# dual_opamp_proto_board.net
KiCad netlist of a schematic drawn in EAGLE
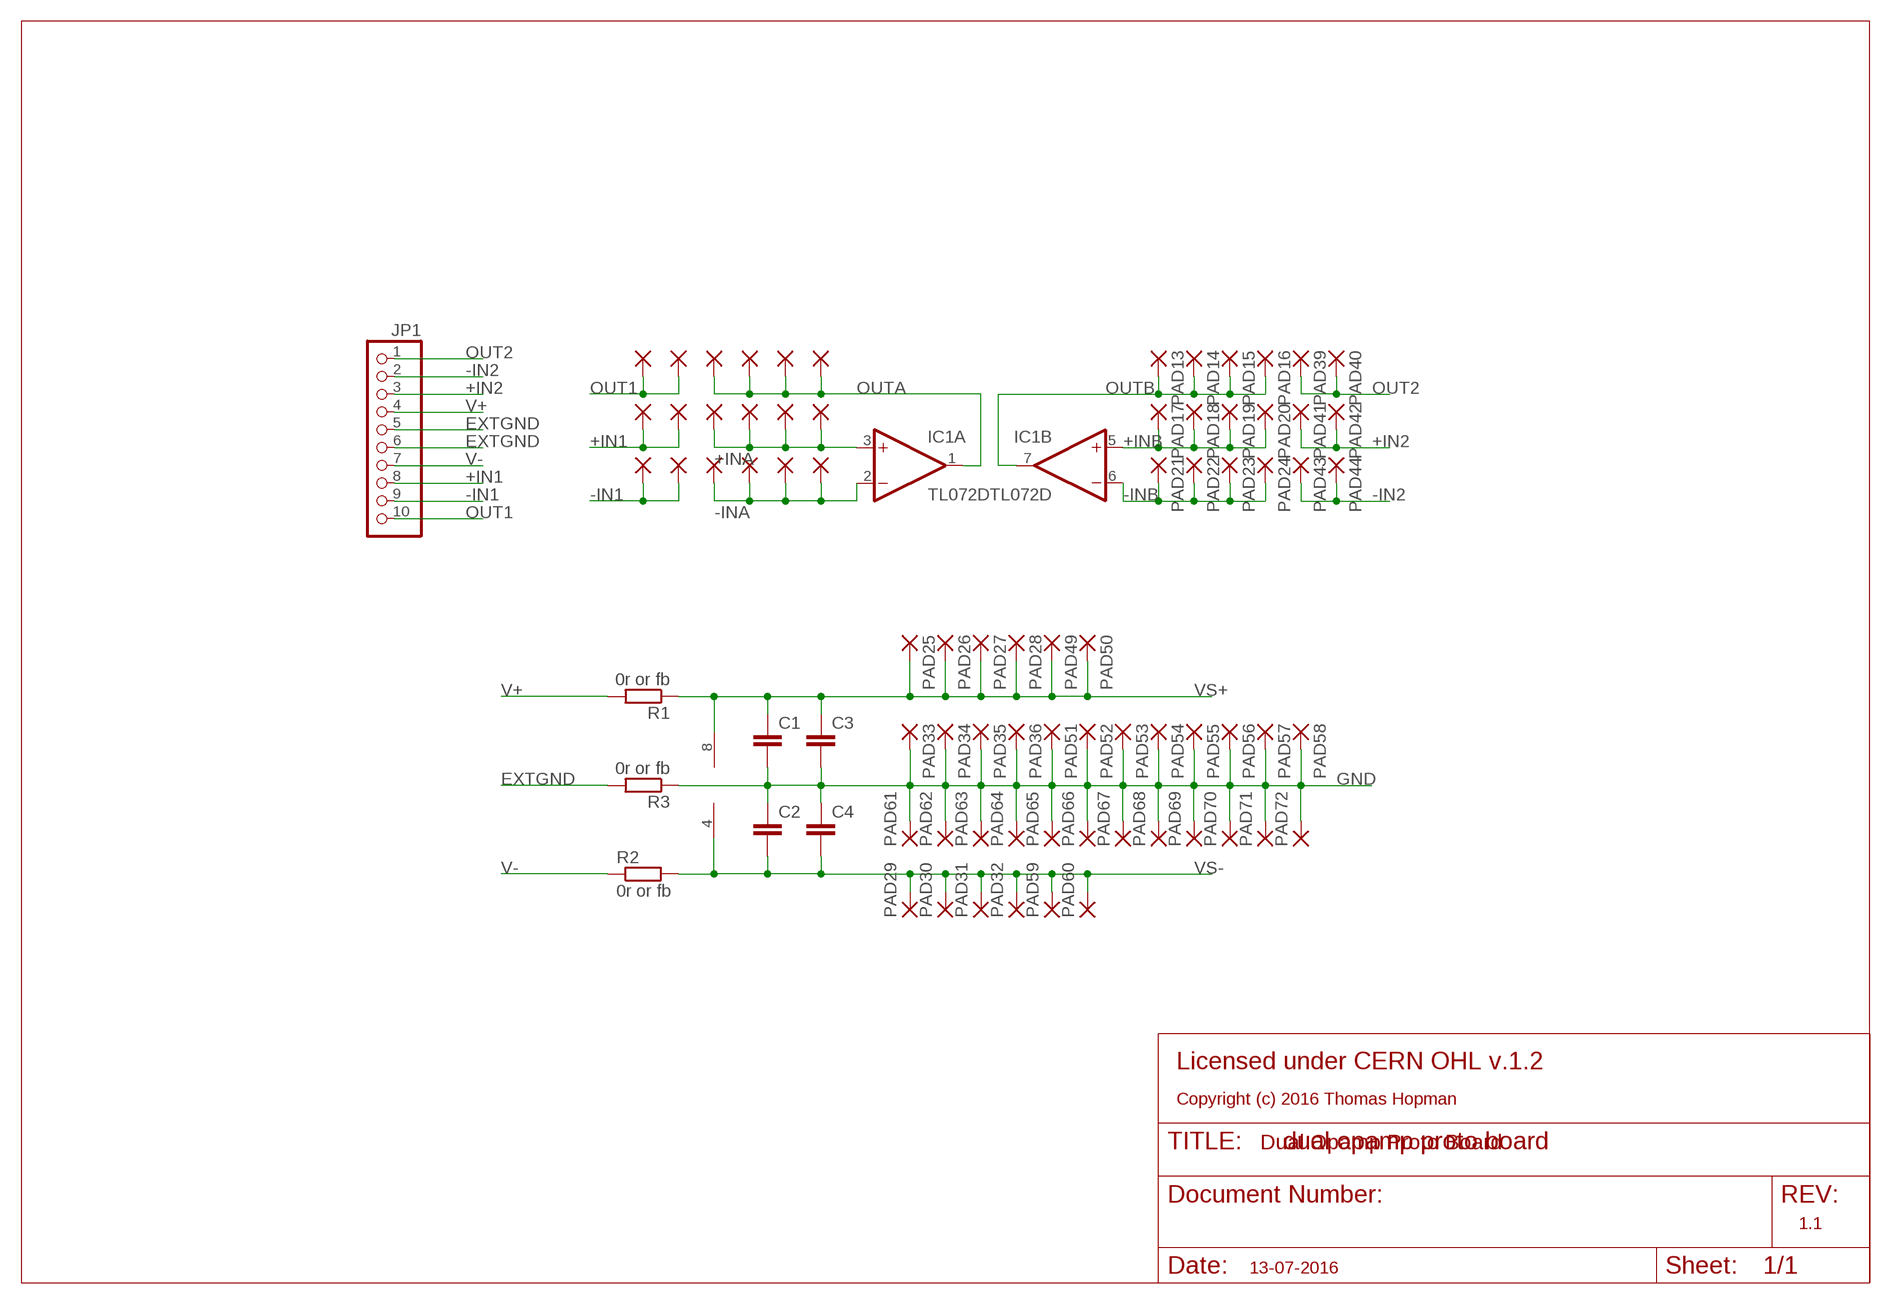
[diagram p0: schematic, sheet 1]

(export (version "E")
  (design (tool "Eeschema 10.0.6"))
  (components
    (comp (ref "C1")
      (value "C-EUC0805")
      (footprint "eagle-import:C0805")
      (libsource (lib "eagle-import") (part "C-EUC0805"))
    )
    (comp (ref "C2")
      (value "C-EUC0805")
      (footprint "eagle-import:C0805")
      (libsource (lib "eagle-import") (part "C-EUC0805"))
    )
    (comp (ref "C3")
      (value "C-EUC1206")
      (footprint "eagle-import:C1206")
      (libsource (lib "eagle-import") (part "C-EUC1206"))
    )
    (comp (ref "C4")
      (value "C-EUC1206")
      (footprint "eagle-import:C1206")
      (libsource (lib "eagle-import") (part "C-EUC1206"))
    )
    (comp (ref "IC1")
      (value "TL072D")
      (footprint "eagle-import:SO08")
      (libsource (lib "eagle-import") (part "TL072D"))
    )
    (comp (ref "JP1")
      (value "PINHD-1X10")
      (footprint "eagle-import:1X10")
      (libsource (lib "eagle-import") (part "PINHD-1X10"))
    )
    (comp (ref "PAD1")
      (value "2,15/1,0")
      (footprint "eagle-import:2,15_1,0")
      (libsource (lib "eagle-import") (part "2,15/1,0"))
    )
    (comp (ref "PAD2")
      (value "2,15/1,0")
      (footprint "eagle-import:2,15_1,0")
      (libsource (lib "eagle-import") (part "2,15/1,0"))
    )
    (comp (ref "PAD3")
      (value "2,15/1,0")
      (footprint "eagle-import:2,15_1,0")
      (libsource (lib "eagle-import") (part "2,15/1,0"))
    )
    (comp (ref "PAD4")
      (value "2,15/1,0")
      (footprint "eagle-import:2,15_1,0")
      (libsource (lib "eagle-import") (part "2,15/1,0"))
    )
    (comp (ref "PAD5")
      (value "2,15/1,0")
      (footprint "eagle-import:2,15_1,0")
      (libsource (lib "eagle-import") (part "2,15/1,0"))
    )
    (comp (ref "PAD6")
      (value "2,15/1,0")
      (footprint "eagle-import:2,15_1,0")
      (libsource (lib "eagle-import") (part "2,15/1,0"))
    )
    (comp (ref "PAD7")
      (value "2,15/1,0")
      (footprint "eagle-import:2,15_1,0")
      (libsource (lib "eagle-import") (part "2,15/1,0"))
    )
    (comp (ref "PAD8")
      (value "2,15/1,0")
      (footprint "eagle-import:2,15_1,0")
      (libsource (lib "eagle-import") (part "2,15/1,0"))
    )
    (comp (ref "PAD9")
      (value "2,15/1,0")
      (footprint "eagle-import:2,15_1,0")
      (libsource (lib "eagle-import") (part "2,15/1,0"))
    )
    (comp (ref "PAD10")
      (value "2,15/1,0")
      (footprint "eagle-import:2,15_1,0")
      (libsource (lib "eagle-import") (part "2,15/1,0"))
    )
    (comp (ref "PAD11")
      (value "2,15/1,0")
      (footprint "eagle-import:2,15_1,0")
      (libsource (lib "eagle-import") (part "2,15/1,0"))
    )
    (comp (ref "PAD12")
      (value "2,15/1,0")
      (footprint "eagle-import:2,15_1,0")
      (libsource (lib "eagle-import") (part "2,15/1,0"))
    )
    (comp (ref "PAD13")
      (value "2,15/1,0")
      (footprint "eagle-import:2,15_1,0")
      (libsource (lib "eagle-import") (part "2,15/1,0"))
    )
    (comp (ref "PAD14")
      (value "2,15/1,0")
      (footprint "eagle-import:2,15_1,0")
      (libsource (lib "eagle-import") (part "2,15/1,0"))
    )
    (comp (ref "PAD15")
      (value "2,15/1,0")
      (footprint "eagle-import:2,15_1,0")
      (libsource (lib "eagle-import") (part "2,15/1,0"))
    )
    (comp (ref "PAD16")
      (value "2,15/1,0")
      (footprint "eagle-import:2,15_1,0")
      (libsource (lib "eagle-import") (part "2,15/1,0"))
    )
    (comp (ref "PAD17")
      (value "2,15/1,0")
      (footprint "eagle-import:2,15_1,0")
      (libsource (lib "eagle-import") (part "2,15/1,0"))
    )
    (comp (ref "PAD18")
      (value "2,15/1,0")
      (footprint "eagle-import:2,15_1,0")
      (libsource (lib "eagle-import") (part "2,15/1,0"))
    )
    (comp (ref "PAD19")
      (value "2,15/1,0")
      (footprint "eagle-import:2,15_1,0")
      (libsource (lib "eagle-import") (part "2,15/1,0"))
    )
    (comp (ref "PAD20")
      (value "2,15/1,0")
      (footprint "eagle-import:2,15_1,0")
      (libsource (lib "eagle-import") (part "2,15/1,0"))
    )
    (comp (ref "PAD21")
      (value "2,15/1,0")
      (footprint "eagle-import:2,15_1,0")
      (libsource (lib "eagle-import") (part "2,15/1,0"))
    )
    (comp (ref "PAD22")
      (value "2,15/1,0")
      (footprint "eagle-import:2,15_1,0")
      (libsource (lib "eagle-import") (part "2,15/1,0"))
    )
    (comp (ref "PAD23")
      (value "2,15/1,0")
      (footprint "eagle-import:2,15_1,0")
      (libsource (lib "eagle-import") (part "2,15/1,0"))
    )
    (comp (ref "PAD24")
      (value "2,15/1,0")
      (footprint "eagle-import:2,15_1,0")
      (libsource (lib "eagle-import") (part "2,15/1,0"))
    )
    (comp (ref "PAD25")
      (value "2,15/1,0")
      (footprint "eagle-import:2,15_1,0")
      (libsource (lib "eagle-import") (part "2,15/1,0"))
    )
    (comp (ref "PAD26")
      (value "2,15/1,0")
      (footprint "eagle-import:2,15_1,0")
      (libsource (lib "eagle-import") (part "2,15/1,0"))
    )
    (comp (ref "PAD27")
      (value "2,15/1,0")
      (footprint "eagle-import:2,15_1,0")
      (libsource (lib "eagle-import") (part "2,15/1,0"))
    )
    (comp (ref "PAD28")
      (value "2,15/1,0")
      (footprint "eagle-import:2,15_1,0")
      (libsource (lib "eagle-import") (part "2,15/1,0"))
    )
    (comp (ref "PAD29")
      (value "2,15/1,0")
      (footprint "eagle-import:2,15_1,0")
      (libsource (lib "eagle-import") (part "2,15/1,0"))
    )
    (comp (ref "PAD30")
      (value "2,15/1,0")
      (footprint "eagle-import:2,15_1,0")
      (libsource (lib "eagle-import") (part "2,15/1,0"))
    )
    (comp (ref "PAD31")
      (value "2,15/1,0")
      (footprint "eagle-import:2,15_1,0")
      (libsource (lib "eagle-import") (part "2,15/1,0"))
    )
    (comp (ref "PAD32")
      (value "2,15/1,0")
      (footprint "eagle-import:2,15_1,0")
      (libsource (lib "eagle-import") (part "2,15/1,0"))
    )
    (comp (ref "PAD33")
      (value "2,15/1,0")
      (footprint "eagle-import:2,15_1,0")
      (libsource (lib "eagle-import") (part "2,15/1,0"))
    )
    (comp (ref "PAD34")
      (value "2,15/1,0")
      (footprint "eagle-import:2,15_1,0")
      (libsource (lib "eagle-import") (part "2,15/1,0"))
    )
    (comp (ref "PAD35")
      (value "2,15/1,0")
      (footprint "eagle-import:2,15_1,0")
      (libsource (lib "eagle-import") (part "2,15/1,0"))
    )
    (comp (ref "PAD36")
      (value "2,15/1,0")
      (footprint "eagle-import:2,15_1,0")
      (libsource (lib "eagle-import") (part "2,15/1,0"))
    )
    (comp (ref "PAD37")
      (value "2,15/1,0")
      (footprint "eagle-import:2,15_1,0")
      (libsource (lib "eagle-import") (part "2,15/1,0"))
    )
    (comp (ref "PAD38")
      (value "2,15/1,0")
      (footprint "eagle-import:2,15_1,0")
      (libsource (lib "eagle-import") (part "2,15/1,0"))
    )
    (comp (ref "PAD39")
      (value "2,15/1,0")
      (footprint "eagle-import:2,15_1,0")
      (libsource (lib "eagle-import") (part "2,15/1,0"))
    )
    (comp (ref "PAD40")
      (value "2,15/1,0")
      (footprint "eagle-import:2,15_1,0")
      (libsource (lib "eagle-import") (part "2,15/1,0"))
    )
    (comp (ref "PAD41")
      (value "2,15/1,0")
      (footprint "eagle-import:2,15_1,0")
      (libsource (lib "eagle-import") (part "2,15/1,0"))
    )
    (comp (ref "PAD42")
      (value "2,15/1,0")
      (footprint "eagle-import:2,15_1,0")
      (libsource (lib "eagle-import") (part "2,15/1,0"))
    )
    (comp (ref "PAD43")
      (value "2,15/1,0")
      (footprint "eagle-import:2,15_1,0")
      (libsource (lib "eagle-import") (part "2,15/1,0"))
    )
    (comp (ref "PAD44")
      (value "2,15/1,0")
      (footprint "eagle-import:2,15_1,0")
      (libsource (lib "eagle-import") (part "2,15/1,0"))
    )
    (comp (ref "PAD45")
      (value "2,15/1,0")
      (footprint "eagle-import:2,15_1,0")
      (libsource (lib "eagle-import") (part "2,15/1,0"))
    )
    (comp (ref "PAD46")
      (value "2,15/1,0")
      (footprint "eagle-import:2,15_1,0")
      (libsource (lib "eagle-import") (part "2,15/1,0"))
    )
    (comp (ref "PAD47")
      (value "2,15/1,0")
      (footprint "eagle-import:2,15_1,0")
      (libsource (lib "eagle-import") (part "2,15/1,0"))
    )
    (comp (ref "PAD48")
      (value "2,15/1,0")
      (footprint "eagle-import:2,15_1,0")
      (libsource (lib "eagle-import") (part "2,15/1,0"))
    )
    (comp (ref "PAD49")
      (value "2,15/1,0")
      (footprint "eagle-import:2,15_1,0")
      (libsource (lib "eagle-import") (part "2,15/1,0"))
    )
    (comp (ref "PAD50")
      (value "2,15/1,0")
      (footprint "eagle-import:2,15_1,0")
      (libsource (lib "eagle-import") (part "2,15/1,0"))
    )
    (comp (ref "PAD51")
      (value "2,15/1,0")
      (footprint "eagle-import:2,15_1,0")
      (libsource (lib "eagle-import") (part "2,15/1,0"))
    )
    (comp (ref "PAD52")
      (value "2,15/1,0")
      (footprint "eagle-import:2,15_1,0")
      (libsource (lib "eagle-import") (part "2,15/1,0"))
    )
    (comp (ref "PAD53")
      (value "2,15/1,0")
      (footprint "eagle-import:2,15_1,0")
      (libsource (lib "eagle-import") (part "2,15/1,0"))
    )
    (comp (ref "PAD54")
      (value "2,15/1,0")
      (footprint "eagle-import:2,15_1,0")
      (libsource (lib "eagle-import") (part "2,15/1,0"))
    )
    (comp (ref "PAD55")
      (value "2,15/1,0")
      (footprint "eagle-import:2,15_1,0")
      (libsource (lib "eagle-import") (part "2,15/1,0"))
    )
    (comp (ref "PAD56")
      (value "2,15/1,0")
      (footprint "eagle-import:2,15_1,0")
      (libsource (lib "eagle-import") (part "2,15/1,0"))
    )
    (comp (ref "PAD57")
      (value "2,15/1,0")
      (footprint "eagle-import:2,15_1,0")
      (libsource (lib "eagle-import") (part "2,15/1,0"))
    )
    (comp (ref "PAD58")
      (value "2,15/1,0")
      (footprint "eagle-import:2,15_1,0")
      (libsource (lib "eagle-import") (part "2,15/1,0"))
    )
    (comp (ref "PAD59")
      (value "2,15/1,0")
      (footprint "eagle-import:2,15_1,0")
      (libsource (lib "eagle-import") (part "2,15/1,0"))
    )
    (comp (ref "PAD60")
      (value "2,15/1,0")
      (footprint "eagle-import:2,15_1,0")
      (libsource (lib "eagle-import") (part "2,15/1,0"))
    )
    (comp (ref "PAD61")
      (value "2,15/1,0")
      (footprint "eagle-import:2,15_1,0")
      (libsource (lib "eagle-import") (part "2,15/1,0"))
    )
    (comp (ref "PAD62")
      (value "2,15/1,0")
      (footprint "eagle-import:2,15_1,0")
      (libsource (lib "eagle-import") (part "2,15/1,0"))
    )
    (comp (ref "PAD63")
      (value "2,15/1,0")
      (footprint "eagle-import:2,15_1,0")
      (libsource (lib "eagle-import") (part "2,15/1,0"))
    )
    (comp (ref "PAD64")
      (value "2,15/1,0")
      (footprint "eagle-import:2,15_1,0")
      (libsource (lib "eagle-import") (part "2,15/1,0"))
    )
    (comp (ref "PAD65")
      (value "2,15/1,0")
      (footprint "eagle-import:2,15_1,0")
      (libsource (lib "eagle-import") (part "2,15/1,0"))
    )
    (comp (ref "PAD66")
      (value "2,15/1,0")
      (footprint "eagle-import:2,15_1,0")
      (libsource (lib "eagle-import") (part "2,15/1,0"))
    )
    (comp (ref "PAD67")
      (value "2,15/1,0")
      (footprint "eagle-import:2,15_1,0")
      (libsource (lib "eagle-import") (part "2,15/1,0"))
    )
    (comp (ref "PAD68")
      (value "2,15/1,0")
      (footprint "eagle-import:2,15_1,0")
      (libsource (lib "eagle-import") (part "2,15/1,0"))
    )
    (comp (ref "PAD69")
      (value "2,15/1,0")
      (footprint "eagle-import:2,15_1,0")
      (libsource (lib "eagle-import") (part "2,15/1,0"))
    )
    (comp (ref "PAD70")
      (value "2,15/1,0")
      (footprint "eagle-import:2,15_1,0")
      (libsource (lib "eagle-import") (part "2,15/1,0"))
    )
    (comp (ref "PAD71")
      (value "2,15/1,0")
      (footprint "eagle-import:2,15_1,0")
      (libsource (lib "eagle-import") (part "2,15/1,0"))
    )
    (comp (ref "PAD72")
      (value "2,15/1,0")
      (footprint "eagle-import:2,15_1,0")
      (libsource (lib "eagle-import") (part "2,15/1,0"))
    )
    (comp (ref "R1")
      (value "0r or fb")
      (footprint "eagle-import:R0805")
      (libsource (lib "eagle-import") (part "R-EU_R0805"))
    )
    (comp (ref "R2")
      (value "0r or fb")
      (footprint "eagle-import:R0805")
      (libsource (lib "eagle-import") (part "R-EU_R0805"))
    )
    (comp (ref "R3")
      (value "0r or fb")
      (footprint "eagle-import:R0805")
      (libsource (lib "eagle-import") (part "R-EU_R0805"))
    )
  )
  (nets
    (net (code "1") (name "/+IN1") (class "Default")
      (node (ref "JP1") (pin "8") (pinfunction "8_8") (pintype "passive"))
      (node (ref "PAD45") (pin "1") (pinfunction "P_1") (pintype "passive"))
      (node (ref "PAD46") (pin "1") (pinfunction "P_1") (pintype "passive"))
    )
    (net (code "2") (name "/+IN2") (class "Default")
      (node (ref "JP1") (pin "3") (pinfunction "3_3") (pintype "passive"))
      (node (ref "PAD41") (pin "1") (pinfunction "P_1") (pintype "passive"))
      (node (ref "PAD42") (pin "1") (pinfunction "P_1") (pintype "passive"))
    )
    (net (code "3") (name "/+INA") (class "Default")
      (node (ref "IC1") (pin "3") (pinfunction "+IN_3") (pintype "input"))
      (node (ref "PAD5") (pin "1") (pinfunction "P_1") (pintype "passive"))
      (node (ref "PAD6") (pin "1") (pinfunction "P_1") (pintype "passive"))
      (node (ref "PAD7") (pin "1") (pinfunction "P_1") (pintype "passive"))
      (node (ref "PAD8") (pin "1") (pinfunction "P_1") (pintype "passive"))
    )
    (net (code "4") (name "/+INB") (class "Default")
      (node (ref "IC1") (pin "5") (pinfunction "+IN_5") (pintype "input"))
      (node (ref "PAD17") (pin "1") (pinfunction "P_1") (pintype "passive"))
      (node (ref "PAD18") (pin "1") (pinfunction "P_1") (pintype "passive"))
      (node (ref "PAD19") (pin "1") (pinfunction "P_1") (pintype "passive"))
      (node (ref "PAD20") (pin "1") (pinfunction "P_1") (pintype "passive"))
    )
    (net (code "5") (name "/-IN1") (class "Default")
      (node (ref "JP1") (pin "9") (pinfunction "9_9") (pintype "passive"))
      (node (ref "PAD47") (pin "1") (pinfunction "P_1") (pintype "passive"))
      (node (ref "PAD48") (pin "1") (pinfunction "P_1") (pintype "passive"))
    )
    (net (code "6") (name "/-IN2") (class "Default")
      (node (ref "JP1") (pin "2") (pinfunction "2_2") (pintype "passive"))
      (node (ref "PAD43") (pin "1") (pinfunction "P_1") (pintype "passive"))
      (node (ref "PAD44") (pin "1") (pinfunction "P_1") (pintype "passive"))
    )
    (net (code "7") (name "/-INA") (class "Default")
      (node (ref "IC1") (pin "2") (pinfunction "-IN_2") (pintype "input"))
      (node (ref "PAD10") (pin "1") (pinfunction "P_1") (pintype "passive"))
      (node (ref "PAD11") (pin "1") (pinfunction "P_1") (pintype "passive"))
      (node (ref "PAD12") (pin "1") (pinfunction "P_1") (pintype "passive"))
      (node (ref "PAD9") (pin "1") (pinfunction "P_1") (pintype "passive"))
    )
    (net (code "8") (name "/-INB") (class "Default")
      (node (ref "IC1") (pin "6") (pinfunction "-IN_6") (pintype "input"))
      (node (ref "PAD21") (pin "1") (pinfunction "P_1") (pintype "passive"))
      (node (ref "PAD22") (pin "1") (pinfunction "P_1") (pintype "passive"))
      (node (ref "PAD23") (pin "1") (pinfunction "P_1") (pintype "passive"))
      (node (ref "PAD24") (pin "1") (pinfunction "P_1") (pintype "passive"))
    )
    (net (code "9") (name "/EXTGND") (class "Default")
      (node (ref "JP1") (pin "5") (pinfunction "5_5") (pintype "passive"))
      (node (ref "JP1") (pin "6") (pinfunction "6_6") (pintype "passive"))
      (node (ref "R3") (pin "2") (pinfunction "2_2") (pintype "passive"))
    )
    (net (code "10") (name "/GND") (class "Default")
      (node (ref "C1") (pin "2") (pinfunction "2_2") (pintype "passive"))
      (node (ref "C2") (pin "1") (pinfunction "1_1") (pintype "passive"))
      (node (ref "C3") (pin "2") (pinfunction "2_2") (pintype "passive"))
      (node (ref "C4") (pin "1") (pinfunction "1_1") (pintype "passive"))
      (node (ref "PAD33") (pin "1") (pinfunction "P_1") (pintype "passive"))
      (node (ref "PAD34") (pin "1") (pinfunction "P_1") (pintype "passive"))
      (node (ref "PAD35") (pin "1") (pinfunction "P_1") (pintype "passive"))
      (node (ref "PAD36") (pin "1") (pinfunction "P_1") (pintype "passive"))
      (node (ref "PAD51") (pin "1") (pinfunction "P_1") (pintype "passive"))
      (node (ref "PAD52") (pin "1") (pinfunction "P_1") (pintype "passive"))
      (node (ref "PAD53") (pin "1") (pinfunction "P_1") (pintype "passive"))
      (node (ref "PAD54") (pin "1") (pinfunction "P_1") (pintype "passive"))
      (node (ref "PAD55") (pin "1") (pinfunction "P_1") (pintype "passive"))
      (node (ref "PAD56") (pin "1") (pinfunction "P_1") (pintype "passive"))
      (node (ref "PAD57") (pin "1") (pinfunction "P_1") (pintype "passive"))
      (node (ref "PAD58") (pin "1") (pinfunction "P_1") (pintype "passive"))
      (node (ref "PAD61") (pin "1") (pinfunction "P_1") (pintype "passive"))
      (node (ref "PAD62") (pin "1") (pinfunction "P_1") (pintype "passive"))
      (node (ref "PAD63") (pin "1") (pinfunction "P_1") (pintype "passive"))
      (node (ref "PAD64") (pin "1") (pinfunction "P_1") (pintype "passive"))
      (node (ref "PAD65") (pin "1") (pinfunction "P_1") (pintype "passive"))
      (node (ref "PAD66") (pin "1") (pinfunction "P_1") (pintype "passive"))
      (node (ref "PAD67") (pin "1") (pinfunction "P_1") (pintype "passive"))
      (node (ref "PAD68") (pin "1") (pinfunction "P_1") (pintype "passive"))
      (node (ref "PAD69") (pin "1") (pinfunction "P_1") (pintype "passive"))
      (node (ref "PAD70") (pin "1") (pinfunction "P_1") (pintype "passive"))
      (node (ref "PAD71") (pin "1") (pinfunction "P_1") (pintype "passive"))
      (node (ref "PAD72") (pin "1") (pinfunction "P_1") (pintype "passive"))
      (node (ref "R3") (pin "1") (pinfunction "1_1") (pintype "passive"))
    )
    (net (code "11") (name "/OUT1") (class "Default")
      (node (ref "JP1") (pin "10") (pinfunction "10_10") (pintype "passive"))
      (node (ref "PAD37") (pin "1") (pinfunction "P_1") (pintype "passive"))
      (node (ref "PAD38") (pin "1") (pinfunction "P_1") (pintype "passive"))
    )
    (net (code "12") (name "/OUT2") (class "Default")
      (node (ref "JP1") (pin "1") (pinfunction "1_1") (pintype "passive"))
      (node (ref "PAD39") (pin "1") (pinfunction "P_1") (pintype "passive"))
      (node (ref "PAD40") (pin "1") (pinfunction "P_1") (pintype "passive"))
    )
    (net (code "13") (name "/OUTA") (class "Default")
      (node (ref "IC1") (pin "1") (pinfunction "OUT_1") (pintype "output"))
      (node (ref "PAD1") (pin "1") (pinfunction "P_1") (pintype "passive"))
      (node (ref "PAD2") (pin "1") (pinfunction "P_1") (pintype "passive"))
      (node (ref "PAD3") (pin "1") (pinfunction "P_1") (pintype "passive"))
      (node (ref "PAD4") (pin "1") (pinfunction "P_1") (pintype "passive"))
    )
    (net (code "14") (name "/OUTB") (class "Default")
      (node (ref "IC1") (pin "7") (pinfunction "OUT_7") (pintype "output"))
      (node (ref "PAD13") (pin "1") (pinfunction "P_1") (pintype "passive"))
      (node (ref "PAD14") (pin "1") (pinfunction "P_1") (pintype "passive"))
      (node (ref "PAD15") (pin "1") (pinfunction "P_1") (pintype "passive"))
      (node (ref "PAD16") (pin "1") (pinfunction "P_1") (pintype "passive"))
    )
    (net (code "15") (name "/V+") (class "Default")
      (node (ref "JP1") (pin "4") (pinfunction "4_4") (pintype "passive"))
      (node (ref "R1") (pin "2") (pinfunction "2_2") (pintype "passive"))
    )
    (net (code "16") (name "/V-") (class "Default")
      (node (ref "JP1") (pin "7") (pinfunction "7_7") (pintype "passive"))
      (node (ref "R2") (pin "1") (pinfunction "1_1") (pintype "passive"))
    )
    (net (code "17") (name "/VS+") (class "Default")
      (node (ref "C1") (pin "1") (pinfunction "1_1") (pintype "passive"))
      (node (ref "C3") (pin "1") (pinfunction "1_1") (pintype "passive"))
      (node (ref "IC1") (pin "8") (pinfunction "V+_8") (pintype "power_in"))
      (node (ref "PAD25") (pin "1") (pinfunction "P_1") (pintype "passive"))
      (node (ref "PAD26") (pin "1") (pinfunction "P_1") (pintype "passive"))
      (node (ref "PAD27") (pin "1") (pinfunction "P_1") (pintype "passive"))
      (node (ref "PAD28") (pin "1") (pinfunction "P_1") (pintype "passive"))
      (node (ref "PAD49") (pin "1") (pinfunction "P_1") (pintype "passive"))
      (node (ref "PAD50") (pin "1") (pinfunction "P_1") (pintype "passive"))
      (node (ref "R1") (pin "1") (pinfunction "1_1") (pintype "passive"))
    )
    (net (code "18") (name "/VS-") (class "Default")
      (node (ref "C2") (pin "2") (pinfunction "2_2") (pintype "passive"))
      (node (ref "C4") (pin "2") (pinfunction "2_2") (pintype "passive"))
      (node (ref "IC1") (pin "4") (pinfunction "V-_4") (pintype "power_in"))
      (node (ref "PAD29") (pin "1") (pinfunction "P_1") (pintype "passive"))
      (node (ref "PAD30") (pin "1") (pinfunction "P_1") (pintype "passive"))
      (node (ref "PAD31") (pin "1") (pinfunction "P_1") (pintype "passive"))
      (node (ref "PAD32") (pin "1") (pinfunction "P_1") (pintype "passive"))
      (node (ref "PAD59") (pin "1") (pinfunction "P_1") (pintype "passive"))
      (node (ref "PAD60") (pin "1") (pinfunction "P_1") (pintype "passive"))
      (node (ref "R2") (pin "2") (pinfunction "2_2") (pintype "passive"))
    )
  )
)
